# Analog_adacus_sch.net
KiCad netlist of a schematic drawn in Altium Designer
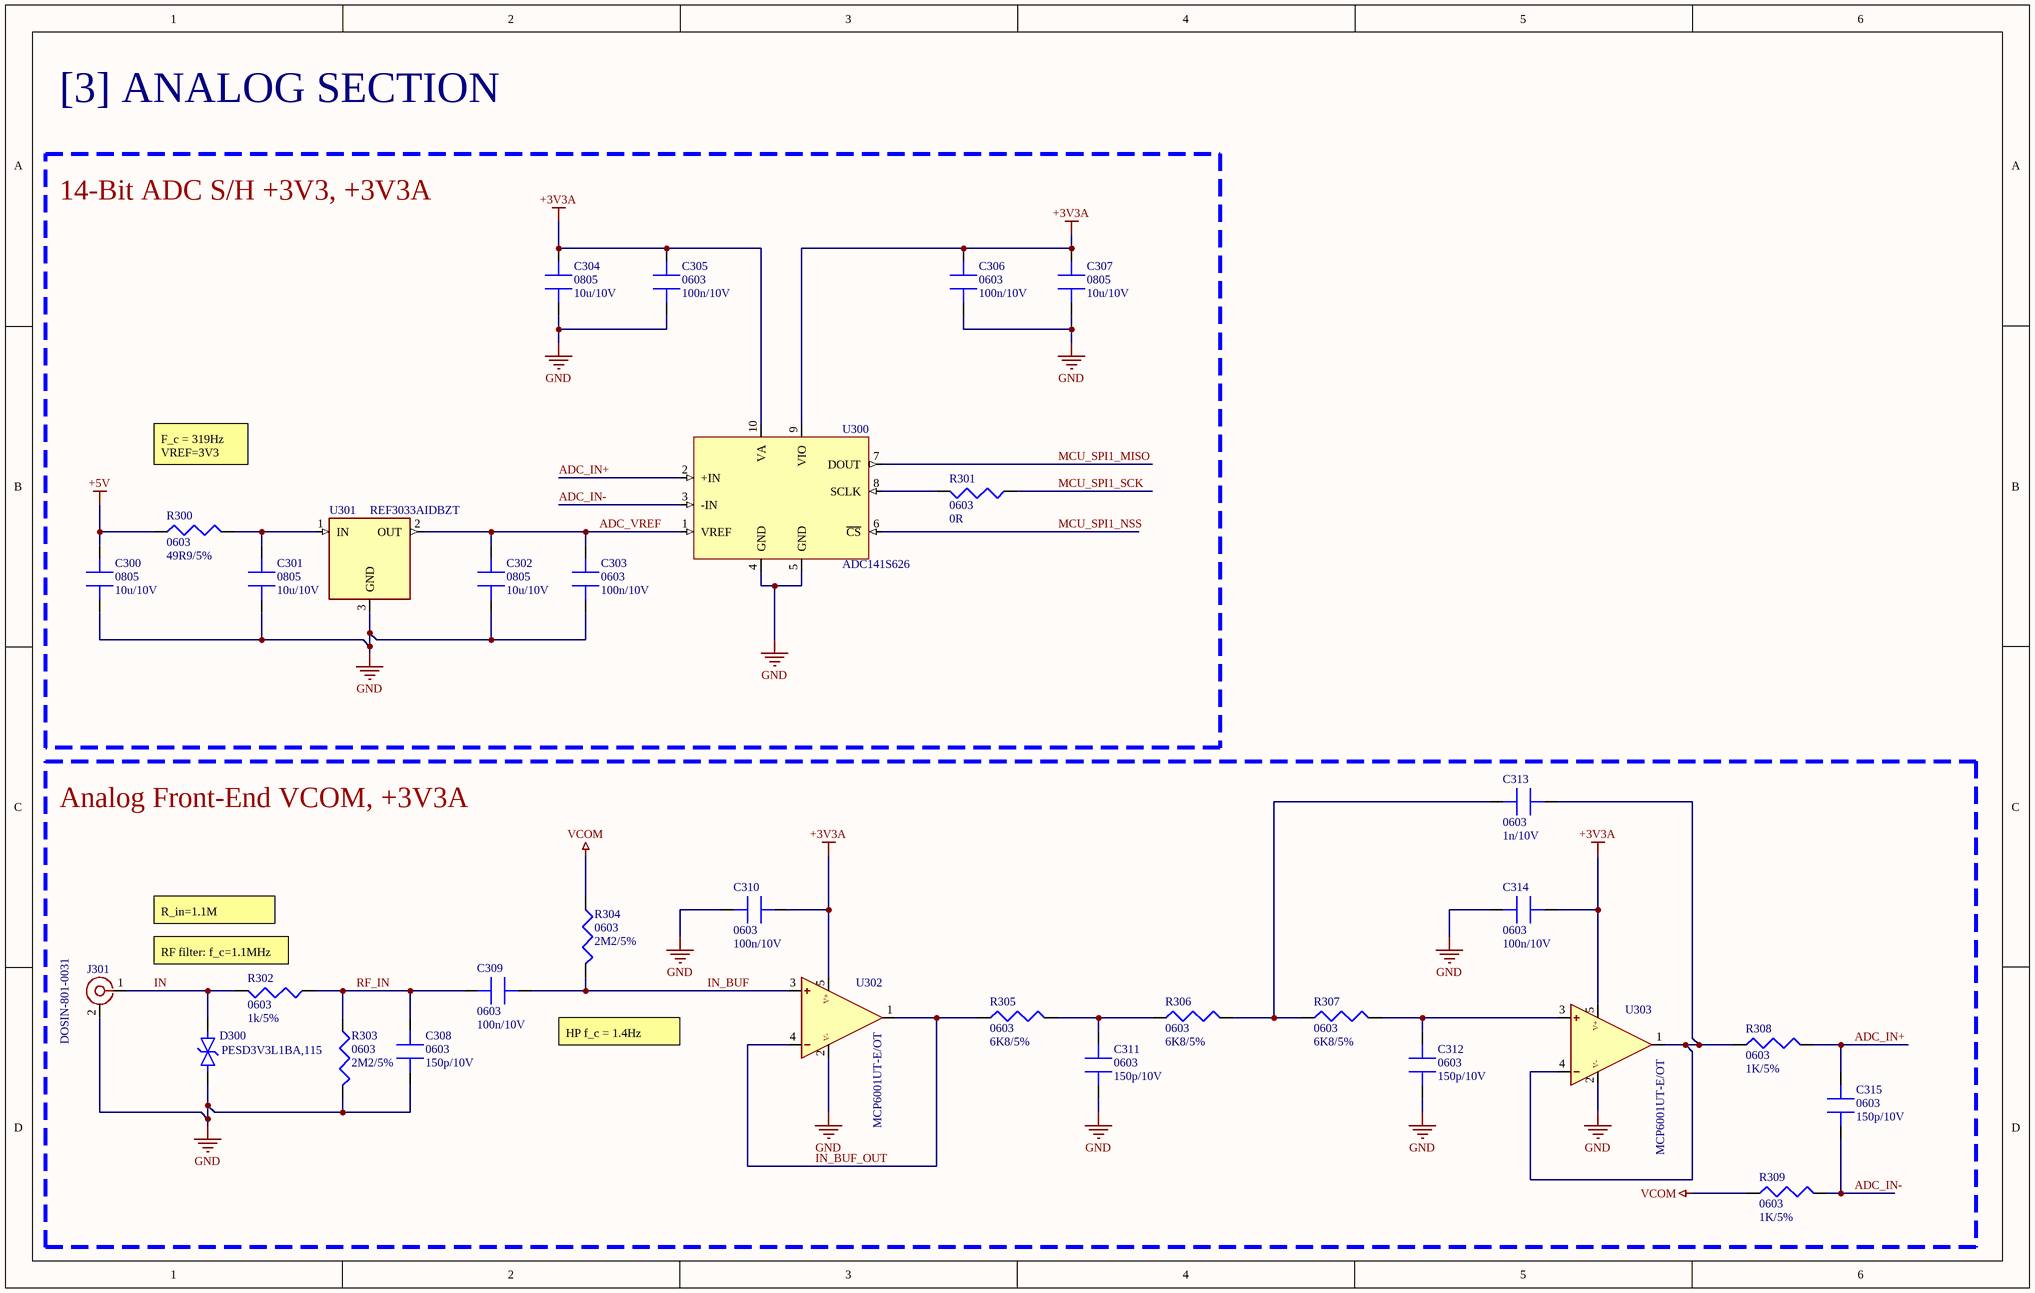
[diagram p0: Analog_adacus_sch.SchDoc]

(export (version "E")
  (design (tool "Eeschema 10.0.6"))
  (components
    (comp (ref "C300")
      (value "10u/10V")
      (footprint "[0805] CAPC2012X09M [A - LD]")
      (description "Standard Capacitor")
      (fields (field (name "PACKAGE") "0805") (field (name "Comment") "Capacitor"))
      (libsource (lib "adacus_schlib") (part "Capacitor"))
    )
    (comp (ref "C301")
      (value "10u/10V")
      (footprint "[0805] CAPC2012X09M [A - LD]")
      (description "Standard Capacitor")
      (fields (field (name "PACKAGE") "0805") (field (name "Comment") "Capacitor"))
      (libsource (lib "adacus_schlib") (part "Capacitor"))
    )
    (comp (ref "C302")
      (value "10u/10V")
      (footprint "[0805] CAPC2012X09M [A - LD]")
      (description "Standard Capacitor")
      (fields (field (name "PACKAGE") "0805") (field (name "Comment") "Capacitor"))
      (libsource (lib "adacus_schlib") (part "Capacitor"))
    )
    (comp (ref "C303")
      (value "100n/10V")
      (footprint "[0603] CAPC1608X10M [A-LD]")
      (description "Standard Capacitor")
      (fields (field (name "PACKAGE") "0603") (field (name "Comment") "Capacitor"))
      (libsource (lib "adacus_schlib") (part "Capacitor"))
    )
    (comp (ref "C304")
      (value "10u/10V")
      (footprint "[0805] CAPC2012X09M [A - LD]")
      (description "Standard Capacitor")
      (fields (field (name "PACKAGE") "0805") (field (name "Comment") "Capacitor"))
      (libsource (lib "adacus_schlib") (part "Capacitor"))
    )
    (comp (ref "C305")
      (value "100n/10V")
      (footprint "[0603] CAPC1608X10M [A-LD]")
      (description "Standard Capacitor")
      (fields (field (name "PACKAGE") "0603") (field (name "Comment") "Capacitor"))
      (libsource (lib "adacus_schlib") (part "Capacitor"))
    )
    (comp (ref "C306")
      (value "100n/10V")
      (footprint "[0603] CAPC1608X10M [A-LD]")
      (description "Standard Capacitor")
      (fields (field (name "PACKAGE") "0603") (field (name "Comment") "Capacitor"))
      (libsource (lib "adacus_schlib") (part "Capacitor"))
    )
    (comp (ref "C307")
      (value "10u/10V")
      (footprint "[0805] CAPC2012X09M [A - LD]")
      (description "Standard Capacitor")
      (fields (field (name "PACKAGE") "0805") (field (name "Comment") "Capacitor"))
      (libsource (lib "adacus_schlib") (part "Capacitor"))
    )
    (comp (ref "C308")
      (value "150p/10V")
      (footprint "[0603] CAPC1608X10M [A-LD]")
      (description "Standard Capacitor")
      (fields (field (name "PACKAGE") "0603") (field (name "Comment") "Capacitor"))
      (libsource (lib "adacus_schlib") (part "Capacitor"))
    )
    (comp (ref "C309")
      (value "100n/10V")
      (footprint "[0603] CAPC1608X10M [A-LD]")
      (description "Standard Capacitor")
      (fields (field (name "PACKAGE") "0603") (field (name "Comment") "Capacitor"))
      (libsource (lib "adacus_schlib") (part "Capacitor"))
    )
    (comp (ref "C310")
      (value "100n/10V")
      (footprint "[0603] CAPC1608X10M [A-LD]")
      (description "Standard Capacitor")
      (fields (field (name "PACKAGE") "0603") (field (name "Comment") "Capacitor"))
      (libsource (lib "adacus_schlib") (part "Capacitor"))
    )
    (comp (ref "C311")
      (value "150p/10V")
      (footprint "[0603] CAPC1608X10M [A-LD]")
      (description "Standard Capacitor")
      (fields (field (name "PACKAGE") "0603") (field (name "Comment") "Capacitor"))
      (libsource (lib "adacus_schlib") (part "Capacitor"))
    )
    (comp (ref "C312")
      (value "150p/10V")
      (footprint "[0603] CAPC1608X10M [A-LD]")
      (description "Standard Capacitor")
      (fields (field (name "PACKAGE") "0603") (field (name "Comment") "Capacitor"))
      (libsource (lib "adacus_schlib") (part "Capacitor"))
    )
    (comp (ref "C313")
      (value "1n/10V")
      (footprint "[0603] CAPC1608X10M [A-LD]")
      (description "Standard Capacitor")
      (fields (field (name "PACKAGE") "0603") (field (name "Comment") "Capacitor"))
      (libsource (lib "adacus_schlib") (part "Capacitor"))
    )
    (comp (ref "C314")
      (value "100n/10V")
      (footprint "[0603] CAPC1608X10M [A-LD]")
      (description "Standard Capacitor")
      (fields (field (name "PACKAGE") "0603") (field (name "Comment") "Capacitor"))
      (libsource (lib "adacus_schlib") (part "Capacitor"))
    )
    (comp (ref "C315")
      (value "150p/10V")
      (footprint "[0603] CAPC1608X10M [A-LD]")
      (description "Standard Capacitor")
      (fields (field (name "PACKAGE") "0603") (field (name "Comment") "Capacitor"))
      (libsource (lib "adacus_schlib") (part "Capacitor"))
    )
    (comp (ref "D300")
      (value "PESD3V3L1BA,115")
      (footprint "SODFL250X110-2M")
      (description "ESD Suppressors / TVS Diodes PESD3V3L1BA/SOD323/SOD2")
      (libsource (lib "adacus_schlib") (part "PESD3V3L1BA,115"))
    )
    (comp (ref "J301")
      (value "DOSIN-801-0031")
      (footprint "DOSIN8010031")
      (description "BNC Board Edge Bend 9.6mm Plugin RF Connectors / Coaxial Connectors")
      (libsource (lib "adacus_schlib") (part "BNC Connector"))
    )
    (comp (ref "R300")
      (value "49R9/5%")
      (footprint "[0603] RESC1608X06M [A-LD]")
      (description "Standard Resistor")
      (fields (field (name "PACKAGE") "0603") (field (name "Comment") "Resistor"))
      (libsource (lib "adacus_schlib") (part "Resistor"))
    )
    (comp (ref "R301")
      (value "0R")
      (footprint "[0603] RESC1608X06M [A-LD]")
      (description "Standard Resistor")
      (fields (field (name "PACKAGE") "0603") (field (name "Comment") "Resistor"))
      (libsource (lib "adacus_schlib") (part "Resistor"))
    )
    (comp (ref "R302")
      (value "1k/5%")
      (footprint "[0603] RESC1608X06M [A-LD]")
      (description "Standard Resistor")
      (fields (field (name "PACKAGE") "0603") (field (name "Comment") "Resistor"))
      (libsource (lib "adacus_schlib") (part "Resistor"))
    )
    (comp (ref "R303")
      (value "2M2/5%")
      (footprint "[0603] RESC1608X06M [A-LD]")
      (description "Standard Resistor")
      (fields (field (name "PACKAGE") "0603") (field (name "Comment") "Resistor"))
      (libsource (lib "adacus_schlib") (part "Resistor"))
    )
    (comp (ref "R304")
      (value "2M2/5%")
      (footprint "[0603] RESC1608X06M [A-LD]")
      (description "Standard Resistor")
      (fields (field (name "PACKAGE") "0603") (field (name "Comment") "Resistor"))
      (libsource (lib "adacus_schlib") (part "Resistor"))
    )
    (comp (ref "R305")
      (value "6K8/5%")
      (footprint "[0603] RESC1608X06M [A-LD]")
      (description "Standard Resistor")
      (fields (field (name "PACKAGE") "0603") (field (name "Comment") "Resistor"))
      (libsource (lib "adacus_schlib") (part "Resistor"))
    )
    (comp (ref "R306")
      (value "6K8/5%")
      (footprint "[0603] RESC1608X06M [A-LD]")
      (description "Standard Resistor")
      (fields (field (name "PACKAGE") "0603") (field (name "Comment") "Resistor"))
      (libsource (lib "adacus_schlib") (part "Resistor"))
    )
    (comp (ref "R307")
      (value "6K8/5%")
      (footprint "[0603] RESC1608X06M [A-LD]")
      (description "Standard Resistor")
      (fields (field (name "PACKAGE") "0603") (field (name "Comment") "Resistor"))
      (libsource (lib "adacus_schlib") (part "Resistor"))
    )
    (comp (ref "R308")
      (value "1K/5%")
      (footprint "[0603] RESC1608X06M [A-LD]")
      (description "Standard Resistor")
      (fields (field (name "PACKAGE") "0603") (field (name "Comment") "Resistor"))
      (libsource (lib "adacus_schlib") (part "Resistor"))
    )
    (comp (ref "R309")
      (value "1K/5%")
      (footprint "[0603] RESC1608X06M [A-LD]")
      (description "Standard Resistor")
      (fields (field (name "PACKAGE") "0603") (field (name "Comment") "Resistor"))
      (libsource (lib "adacus_schlib") (part "Resistor"))
    )
    (comp (ref "U300")
      (value "ADC141S626")
      (footprint "TSSOP50P490X110-10M")
      (libsource (lib "adacus_schlib") (part "ADC141S626"))
    )
    (comp (ref "U301")
      (value "REF3033AIDBZT")
      (footprint "SOT95P237X112-3M")
      (description "Voltage References 3.3V 50ppm/DegC 50uA SOT23-3 Series")
      (libsource (lib "adacus_schlib") (part "REF3033AIDBZT"))
    )
    (comp (ref "U302")
      (value "MCP6001UT-E/OT")
      (footprint "SOT95P270X145-5M")
      (description "Operational Amplifiers - Op Amps Single 1.8V 1MHz")
      (libsource (lib "adacus_schlib") (part "MCP6001UT-E/OT"))
    )
    (comp (ref "U303")
      (value "MCP6001UT-E/OT")
      (footprint "SOT95P270X145-5M")
      (description "Operational Amplifiers - Op Amps Single 1.8V 1MHz")
      (libsource (lib "adacus_schlib") (part "MCP6001UT-E/OT"))
    )
  )
  (nets
    (net (code "1") (name "+3V3A") (class "Default")
      (node (ref "C304") (pin "2") (pinfunction "2_2") (pintype "passive"))
      (node (ref "C305") (pin "2") (pinfunction "2_2") (pintype "passive"))
      (node (ref "C306") (pin "2") (pinfunction "2_2") (pintype "passive"))
      (node (ref "C307") (pin "2") (pinfunction "2_2") (pintype "passive"))
      (node (ref "C310") (pin "1") (pinfunction "1_1") (pintype "passive"))
      (node (ref "C314") (pin "1") (pinfunction "1_1") (pintype "passive"))
      (node (ref "U300") (pin "10") (pinfunction "VA_10") (pintype "power_in"))
      (node (ref "U300") (pin "9") (pinfunction "VIO_9") (pintype "power_in"))
      (node (ref "U302") (pin "5") (pinfunction "VDD_5") (pintype "passive"))
      (node (ref "U303") (pin "5") (pinfunction "VDD_5") (pintype "passive"))
    )
    (net (code "2") (name "+5V") (class "Default")
      (node (ref "C300") (pin "2") (pinfunction "2_2") (pintype "passive"))
      (node (ref "R300") (pin "2") (pinfunction "2_2") (pintype "passive"))
    )
    (net (code "3") (name "/ADC_IN+") (class "Default")
      (node (ref "C315") (pin "2") (pinfunction "2_2") (pintype "passive"))
      (node (ref "R308") (pin "1") (pinfunction "1_1") (pintype "passive"))
      (node (ref "U300") (pin "2") (pinfunction "+IN_2") (pintype "input"))
    )
    (net (code "4") (name "/ADC_IN-") (class "Default")
      (node (ref "C315") (pin "1") (pinfunction "1_1") (pintype "passive"))
      (node (ref "R309") (pin "1") (pinfunction "1_1") (pintype "passive"))
      (node (ref "U300") (pin "3") (pinfunction "-IN_3") (pintype "input"))
    )
    (net (code "5") (name "/ADC_VREF") (class "Default")
      (node (ref "C302") (pin "2") (pinfunction "2_2") (pintype "passive"))
      (node (ref "C303") (pin "2") (pinfunction "2_2") (pintype "passive"))
      (node (ref "U300") (pin "1") (pinfunction "VREF_1") (pintype "input"))
      (node (ref "U301") (pin "2") (pinfunction "OUT_2") (pintype "output"))
    )
    (net (code "6") (name "/IN") (class "Default")
      (node (ref "D300") (pin "2") (pinfunction "2_2") (pintype "passive"))
      (node (ref "J301") (pin "1") (pinfunction "1_1") (pintype "passive"))
      (node (ref "R302") (pin "1") (pinfunction "1_1") (pintype "passive"))
    )
    (net (code "7") (name "/IN_BUF") (class "Default")
      (node (ref "C309") (pin "1") (pinfunction "1_1") (pintype "passive"))
      (node (ref "R304") (pin "1") (pinfunction "1_1") (pintype "passive"))
      (node (ref "U302") (pin "3") (pinfunction "+_3") (pintype "passive"))
    )
    (net (code "8") (name "/IN_BUF_OUT") (class "Default")
      (node (ref "R305") (pin "2") (pinfunction "2_2") (pintype "passive"))
      (node (ref "U302") (pin "1") (pinfunction "OUT_1") (pintype "passive"))
      (node (ref "U302") (pin "4") (pinfunction "-_4") (pintype "passive"))
    )
    (net (code "9") (name "/MCU_SPI1_MISO") (class "Default")
      (node (ref "U300") (pin "7") (pinfunction "DOUT_7") (pintype "output"))
    )
    (net (code "10") (name "/MCU_SPI1_NSS") (class "Default")
      (node (ref "U300") (pin "6") (pinfunction "~{CS}_6") (pintype "input"))
    )
    (net (code "11") (name "/MCU_SPI1_SCK") (class "Default")
      (node (ref "R301") (pin "2") (pinfunction "2_2") (pintype "passive"))
    )
    (net (code "12") (name "/RF_IN") (class "Default")
      (node (ref "C308") (pin "2") (pinfunction "2_2") (pintype "passive"))
      (node (ref "C309") (pin "2") (pinfunction "2_2") (pintype "passive"))
      (node (ref "R302") (pin "2") (pinfunction "2_2") (pintype "passive"))
      (node (ref "R303") (pin "2") (pinfunction "2_2") (pintype "passive"))
    )
    (net (code "13") (name "GND") (class "Default")
      (node (ref "C300") (pin "1") (pinfunction "1_1") (pintype "passive"))
      (node (ref "C301") (pin "1") (pinfunction "1_1") (pintype "passive"))
      (node (ref "C302") (pin "1") (pinfunction "1_1") (pintype "passive"))
      (node (ref "C303") (pin "1") (pinfunction "1_1") (pintype "passive"))
      (node (ref "C304") (pin "1") (pinfunction "1_1") (pintype "passive"))
      (node (ref "C305") (pin "1") (pinfunction "1_1") (pintype "passive"))
      (node (ref "C306") (pin "1") (pinfunction "1_1") (pintype "passive"))
      (node (ref "C307") (pin "1") (pinfunction "1_1") (pintype "passive"))
      (node (ref "C308") (pin "1") (pinfunction "1_1") (pintype "passive"))
      (node (ref "C310") (pin "2") (pinfunction "2_2") (pintype "passive"))
      (node (ref "C311") (pin "1") (pinfunction "1_1") (pintype "passive"))
      (node (ref "C312") (pin "1") (pinfunction "1_1") (pintype "passive"))
      (node (ref "C314") (pin "2") (pinfunction "2_2") (pintype "passive"))
      (node (ref "D300") (pin "1") (pinfunction "1_1") (pintype "passive"))
      (node (ref "J301") (pin "2") (pinfunction "2_2") (pintype "passive"))
      (node (ref "R303") (pin "1") (pinfunction "1_1") (pintype "passive"))
      (node (ref "U300") (pin "4") (pinfunction "GND_4") (pintype "power_in"))
      (node (ref "U300") (pin "5") (pinfunction "GND_5") (pintype "power_in"))
      (node (ref "U301") (pin "3") (pinfunction "GND_3") (pintype "power_in"))
      (node (ref "U302") (pin "2") (pinfunction "VSS_2") (pintype "passive"))
      (node (ref "U303") (pin "2") (pinfunction "VSS_2") (pintype "passive"))
    )
    (net (code "14") (name "Net-(C311-Pad2)") (class "Default")
      (node (ref "C311") (pin "2") (pinfunction "2_2") (pintype "passive"))
      (node (ref "R305") (pin "1") (pinfunction "1_1") (pintype "passive"))
      (node (ref "R306") (pin "2") (pinfunction "2_2") (pintype "passive"))
    )
    (net (code "15") (name "Net-(C313-Pad2)") (class "Default")
      (node (ref "C313") (pin "2") (pinfunction "2_2") (pintype "passive"))
      (node (ref "R306") (pin "1") (pinfunction "1_1") (pintype "passive"))
      (node (ref "R307") (pin "2") (pinfunction "2_2") (pintype "passive"))
    )
    (net (code "16") (name "Net-(U300-SCLK)") (class "Default")
      (node (ref "R301") (pin "1") (pinfunction "1_1") (pintype "passive"))
      (node (ref "U300") (pin "8") (pinfunction "SCLK_8") (pintype "input"))
    )
    (net (code "17") (name "Net-(U301-IN)") (class "Default")
      (node (ref "C301") (pin "2") (pinfunction "2_2") (pintype "passive"))
      (node (ref "R300") (pin "1") (pinfunction "1_1") (pintype "passive"))
      (node (ref "U301") (pin "1") (pinfunction "IN_1") (pintype "input"))
    )
    (net (code "18") (name "Net-(U303-+)") (class "Default")
      (node (ref "C312") (pin "2") (pinfunction "2_2") (pintype "passive"))
      (node (ref "R307") (pin "1") (pinfunction "1_1") (pintype "passive"))
      (node (ref "U303") (pin "3") (pinfunction "+_3") (pintype "passive"))
    )
    (net (code "19") (name "Net-(U303--)") (class "Default")
      (node (ref "C313") (pin "1") (pinfunction "1_1") (pintype "passive"))
      (node (ref "R308") (pin "2") (pinfunction "2_2") (pintype "passive"))
      (node (ref "U303") (pin "1") (pinfunction "OUT_1") (pintype "passive"))
      (node (ref "U303") (pin "4") (pinfunction "-_4") (pintype "passive"))
    )
    (net (code "20") (name "VCOM") (class "Default")
      (node (ref "R304") (pin "2") (pinfunction "2_2") (pintype "passive"))
      (node (ref "R309") (pin "2") (pinfunction "2_2") (pintype "passive"))
    )
  )
)
